# PROC010C_QSPI_Flash_Reference.net
KiCad netlist of a schematic drawn in Altium Designer
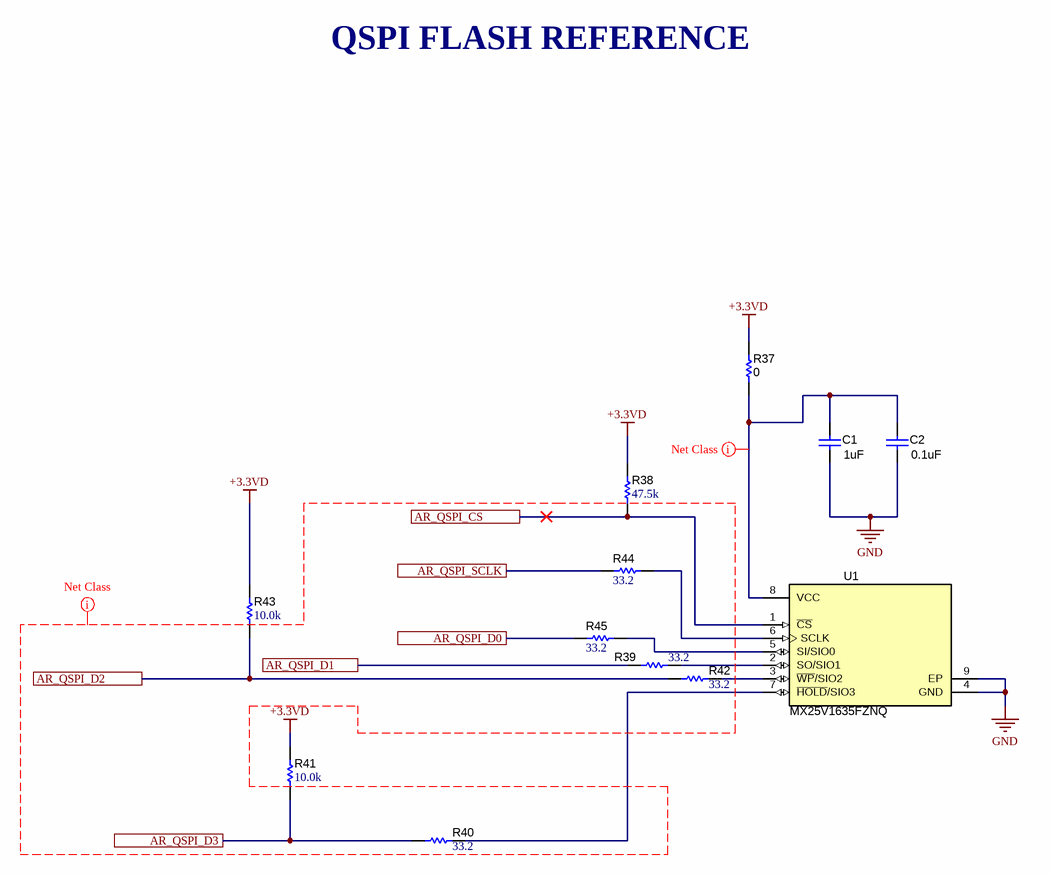
[diagram p0: PROC010C_QSPI_Flash_Reference.SchDoc]

(export (version "E")
  (design (tool "Eeschema 10.0.6"))
  (components
    (comp (ref "C1")
      (value "GCM188R71C105KA64D")
      (footprint "0603")
      (description "CAP, CERM, 1 uF, 16 V, +/- 10%, X7R, AEC-Q200 Grade 1, 0603")
      (fields
        (field (name "MANUFACTURER") "MuRata")
        (field (name "VALUEDISPLAYED") "1uF")
        (field (name "PUBLISHER") "Texas Instruments")
      )
      (libsource (lib "Altium Vault - TI") (part "Capacitor"))
    )
    (comp (ref "C2")
      (value "CGA2B3X7R1H104K050BB")
      (footprint "0402L")
      (description "CAP, CERM, 0.1 uF, 50 V, +/- 10%, X7R, AEC-Q200 Grade 1, 0402")
      (fields
        (field (name "MANUFACTURER") "TDK")
        (field (name "VALUEDISPLAYED") "0.1uF")
        (field (name "PUBLISHER") "Texas Instruments")
      )
      (libsource (lib "Altium Vault - TI") (part "Capacitor"))
    )
    (comp (ref "R37")
      (value "ERJ-2GE0R00X")
      (footprint "0402L")
      (description "RES, 0, 5%, 0.063 W, 0402")
      (fields
        (field (name "MANUFACTURER") "Panasonic")
        (field (name "VALUEDISPLAYED") "0")
        (field (name "PUBLISHER") "Texas Instruments")
      )
      (libsource (lib "Altium Vault - TI") (part "Resistor"))
    )
    (comp (ref "R38")
      (value "CRCW040247K5FKED")
      (footprint "0402L")
      (description "RES, 47.5 k, 1%, 0.063 W, AEC-Q200 Grade 0, 0402")
      (fields (field (name "MANUFACTURER") "Vishay-Dale") (field (name "VALUEDISPLAYED") "47.5k"))
      (libsource (lib "Altium Vault - TI") (part "Resistor"))
    )
    (comp (ref "R39")
      (value "CRCW020133R2FNED")
      (footprint "0201_Silk")
      (description "RES, 33.2, 1%, 0.05 W, 0201")
      (fields (field (name "MANUFACTURER") "Vishay-Dale") (field (name "VALUEDISPLAYED") "33.2"))
      (libsource (lib "Altium Vault - TI") (part "Resistor"))
    )
    (comp (ref "R40")
      (value "CRCW020133R2FNED")
      (footprint "0201_Silk")
      (description "RES, 33.2, 1%, 0.05 W, 0201")
      (fields (field (name "MANUFACTURER") "Vishay-Dale") (field (name "VALUEDISPLAYED") "33.2"))
      (libsource (lib "Altium Vault - TI") (part "Resistor"))
    )
    (comp (ref "R41")
      (value "CRCW040210K0FKED")
      (footprint "0402L")
      (description "RES, 10.0 k, 1%, 0.063 W, AEC-Q200 Grade 0, 0402")
      (fields (field (name "MANUFACTURER") "Vishay-Dale") (field (name "VALUEDISPLAYED") "10.0k"))
      (libsource (lib "Altium Vault - TI") (part "Resistor"))
    )
    (comp (ref "R42")
      (value "CRCW020133R2FNED")
      (footprint "0201_Silk")
      (description "RES, 33.2, 1%, 0.05 W, 0201")
      (fields (field (name "MANUFACTURER") "Vishay-Dale") (field (name "VALUEDISPLAYED") "33.2"))
      (libsource (lib "Altium Vault - TI") (part "Resistor"))
    )
    (comp (ref "R43")
      (value "CRCW040210K0FKED")
      (footprint "0402L")
      (description "RES, 10.0 k, 1%, 0.063 W, AEC-Q200 Grade 0, 0402")
      (fields (field (name "MANUFACTURER") "Vishay-Dale") (field (name "VALUEDISPLAYED") "10.0k"))
      (libsource (lib "Altium Vault - TI") (part "Resistor"))
    )
    (comp (ref "R44")
      (value "CRCW020133R2FNED")
      (footprint "0201_Silk")
      (description "RES, 33.2, 1%, 0.05 W, 0201")
      (fields (field (name "MANUFACTURER") "Vishay-Dale") (field (name "VALUEDISPLAYED") "33.2"))
      (libsource (lib "Altium Vault - TI") (part "Resistor"))
    )
    (comp (ref "R45")
      (value "CRCW020133R2FNED")
      (footprint "0201_Silk")
      (description "RES, 33.2, 1%, 0.05 W, 0201")
      (fields (field (name "MANUFACTURER") "Vishay-Dale") (field (name "VALUEDISPLAYED") "33.2"))
      (libsource (lib "Altium Vault - TI") (part "Resistor"))
    )
    (comp (ref "U1")
      (value "MX25V1635FZNQ")
      (footprint "WSON-8L_6x5MM_EP")
      (description "2.3V-3.6V, 16M-BIT [x 1/x 2/x 4] CMOS FLASH Memory, WSON-8")
      (fields (field (name "MANUFACTURER") "Macronix International Co., LTD"))
      (libsource (lib "Altium Vault - TI") (part "MX25V1635FZ"))
    )
  )
  (nets
    (net (code "1") (name "+3.3VD") (class "Default")
      (node (ref "R37") (pin "1") (pinfunction "1_1") (pintype "passive"))
      (node (ref "R38") (pin "2") (pinfunction "2_2") (pintype "passive"))
      (node (ref "R41") (pin "2") (pinfunction "2_2") (pintype "passive"))
      (node (ref "R43") (pin "2") (pinfunction "2_2") (pintype "passive"))
    )
    (net (code "2") (name "/AR_QSPI_CS") (class "Default")
      (node (ref "R38") (pin "1") (pinfunction "1_1") (pintype "passive"))
      (node (ref "U1") (pin "1") (pinfunction "CS_1") (pintype "input"))
    )
    (net (code "3") (name "/AR_QSPI_D0") (class "Default")
      (node (ref "R45") (pin "2") (pinfunction "2_2") (pintype "passive"))
    )
    (net (code "4") (name "/AR_QSPI_D1") (class "Default")
      (node (ref "R39") (pin "1") (pinfunction "1_1") (pintype "passive"))
    )
    (net (code "5") (name "/AR_QSPI_D2") (class "Default")
      (node (ref "R42") (pin "1") (pinfunction "1_1") (pintype "passive"))
      (node (ref "R43") (pin "1") (pinfunction "1_1") (pintype "passive"))
    )
    (net (code "6") (name "/AR_QSPI_D3") (class "Default")
      (node (ref "R40") (pin "2") (pinfunction "2_2") (pintype "passive"))
      (node (ref "R41") (pin "1") (pinfunction "1_1") (pintype "passive"))
    )
    (net (code "7") (name "/AR_QSPI_SCLK") (class "Default")
      (node (ref "R44") (pin "2") (pinfunction "2_2") (pintype "passive"))
    )
    (net (code "8") (name "GND") (class "Default")
      (node (ref "C1") (pin "1") (pinfunction "1_1") (pintype "passive"))
      (node (ref "C2") (pin "1") (pinfunction "1_1") (pintype "passive"))
      (node (ref "U1") (pin "4") (pinfunction "GND_4") (pintype "power_in"))
      (node (ref "U1") (pin "9") (pinfunction "EP_9") (pintype "passive"))
    )
    (net (code "9") (name "Net-(U1-SCLK)") (class "Default")
      (node (ref "R44") (pin "1") (pinfunction "1_1") (pintype "passive"))
      (node (ref "U1") (pin "6") (pinfunction "SCLK_6") (pintype "input"))
    )
    (net (code "10") (name "Net-(U1-SI{slash}SIO0)") (class "Default")
      (node (ref "R45") (pin "1") (pinfunction "1_1") (pintype "passive"))
      (node (ref "U1") (pin "5") (pinfunction "SI/SIO0_5") (pintype "bidirectional"))
    )
    (net (code "11") (name "Net-(U1-SO{slash}SIO1)") (class "Default")
      (node (ref "R39") (pin "2") (pinfunction "2_2") (pintype "passive"))
      (node (ref "U1") (pin "2") (pinfunction "SO/SIO1_2") (pintype "bidirectional"))
    )
    (net (code "12") (name "Net-(U1-VCC)") (class "Default")
      (node (ref "C1") (pin "2") (pinfunction "2_2") (pintype "passive"))
      (node (ref "C2") (pin "2") (pinfunction "2_2") (pintype "passive"))
      (node (ref "R37") (pin "2") (pinfunction "2_2") (pintype "passive"))
      (node (ref "U1") (pin "8") (pinfunction "VCC_8") (pintype "power_in"))
    )
    (net (code "13") (name "Net-(U1-~{HOLD}{slash}SIO3)") (class "Default")
      (node (ref "R40") (pin "1") (pinfunction "1_1") (pintype "passive"))
      (node (ref "U1") (pin "7") (pinfunction "~{HOLD}/SIO3_7") (pintype "bidirectional"))
    )
    (net (code "14") (name "Net-(U1-~{WP}{slash}SIO2)") (class "Default")
      (node (ref "R42") (pin "2") (pinfunction "2_2") (pintype "passive"))
      (node (ref "U1") (pin "3") (pinfunction "~{WP}/SIO2_3") (pintype "bidirectional"))
    )
  )
)
